# Main.net
KiCad netlist of a schematic drawn in Altium Designer
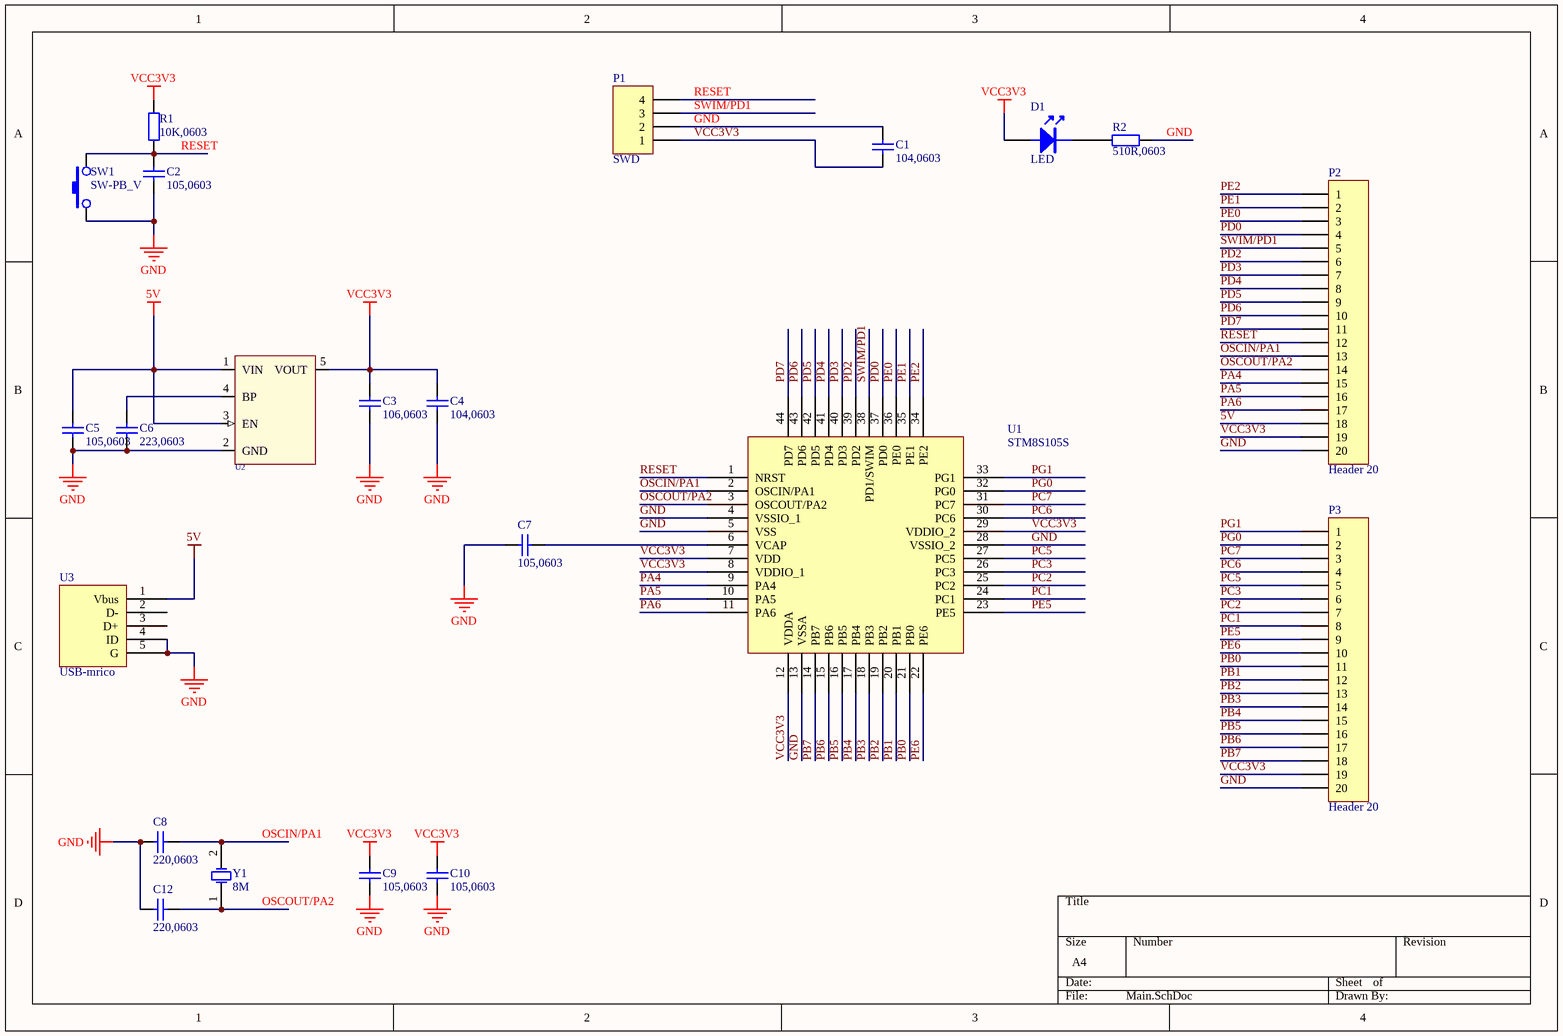
[diagram p0: Main.SchDoc]

(export (version "E")
  (design (tool "Eeschema 10.0.6"))
  (components
    (comp (ref "C1")
      (value "104,0603")
      (footprint "C 0603")
      (description "Capacitor")
      (fields (field (name "PUBLISHER") "Altium Limited"))
      (libsource (lib "STM32F103C8T6") (part "Cap"))
    )
    (comp (ref "C2")
      (value "105,0603")
      (footprint "C 0603")
      (description "Capacitor")
      (fields (field (name "PUBLISHER") "Altium Limited"))
      (libsource (lib "STM32F103C8T6") (part "Cap"))
    )
    (comp (ref "C3")
      (value "106,0603")
      (footprint "C 0603")
      (description "Capacitor")
      (fields (field (name "PUBLISHER") "Altium Limited"))
      (libsource (lib "STM32F103C8T6") (part "Cap"))
    )
    (comp (ref "C4")
      (value "104,0603")
      (footprint "C 0603")
      (description "Capacitor")
      (fields (field (name "PUBLISHER") "Altium Limited"))
      (libsource (lib "STM32F103C8T6") (part "Cap"))
    )
    (comp (ref "C5")
      (value "105,0603")
      (footprint "C 0603")
      (description "Capacitor")
      (fields (field (name "PUBLISHER") "Altium Limited"))
      (libsource (lib "STM32F103C8T6") (part "Cap"))
    )
    (comp (ref "C6")
      (value "223,0603")
      (footprint "C 0603")
      (description "Capacitor")
      (fields (field (name "PUBLISHER") "Altium Limited"))
      (libsource (lib "STM32F103C8T6") (part "Cap"))
    )
    (comp (ref "C7")
      (value "105,0603")
      (footprint "C 0603")
      (description "Capacitor")
      (fields (field (name "PUBLISHER") "Altium Limited"))
      (libsource (lib "STM32F103C8T6") (part "Cap"))
    )
    (comp (ref "C8")
      (value "220,0603")
      (footprint "C 0603")
      (description "Capacitor")
      (fields (field (name "PUBLISHER") "Altium Limited"))
      (libsource (lib "STM32F103C8T6") (part "Cap"))
    )
    (comp (ref "C9")
      (value "105,0603")
      (footprint "C 0603")
      (description "Capacitor")
      (fields (field (name "PUBLISHER") "Altium Limited"))
      (libsource (lib "STM32F103C8T6") (part "Cap"))
    )
    (comp (ref "C10")
      (value "105,0603")
      (footprint "C 0603")
      (description "Capacitor")
      (fields (field (name "PUBLISHER") "Altium Limited"))
      (libsource (lib "STM32F103C8T6") (part "Cap"))
    )
    (comp (ref "C12")
      (value "220,0603")
      (footprint "C 0603")
      (description "Capacitor")
      (fields (field (name "PUBLISHER") "Altium Limited"))
      (libsource (lib "STM32F103C8T6") (part "Cap"))
    )
    (comp (ref "D1") (value "LED") (footprint "LED 0805G") (libsource (lib "STM32F103C8T6") (part "LED")))
    (comp (ref "P1")
      (value "SWD")
      (footprint "HDR-1X4_H")
      (description "Header, 4-Pin")
      (fields (field (name "PUBLISHER") "Altium Limited"))
      (libsource (lib "STM32F103C8T6") (part "Header 4"))
    )
    (comp (ref "P2")
      (value "Header 20")
      (footprint "HDR1X20")
      (description "Header, 20-Pin")
      (fields (field (name "PUBLISHER") "Altium Limited"))
      (libsource (lib "PCB") (part "Header 20"))
    )
    (comp (ref "P3")
      (value "Header 20")
      (footprint "HDR1X20")
      (description "Header, 20-Pin")
      (fields (field (name "PUBLISHER") "Altium Limited"))
      (libsource (lib "PCB") (part "Header 20"))
    )
    (comp (ref "R1")
      (value "10K,0603")
      (footprint "R 0603")
      (description "Resistor")
      (fields (field (name "PUBLISHER") "Altium Limited"))
      (libsource (lib "") (part "Res2_1"))
    )
    (comp (ref "R2")
      (value "510R,0603")
      (footprint "R 0603")
      (description "Resistor")
      (fields (field (name "PUBLISHER") "Altium Limited"))
      (libsource (lib "STM32F103C8T6") (part "Res2"))
    )
    (comp (ref "SW1")
      (value "SW-PB_V")
      (footprint "TSW SMD-3*6*2.5")
      (description "SWITCH")
      (libsource (lib "STM32F103C8T6") (part "SW-PB_V"))
    )
    (comp (ref "U1") (value "STM8S105S") (footprint "PCB:LQFP44") (libsource (lib "PCB") (part "STM8S105S4")))
    (comp (ref "U2")
      (value "RT9193")
      (footprint "SOT23-5L")
      (fields (field (name "ICA_PARTNUM") "$$2191094$$RT9193-15CU5") (field (name "PART NUMBER") "TMP-13"))
      (libsource (lib "STM32F103C8T6") (part "RT9193X_5P"))
    )
    (comp (ref "U3")
      (value "USB-mrico")
      (footprint "USB-micro_B")
      (libsource (lib "PCB_Project_4") (part "usb-STM"))
    )
    (comp (ref "Y1")
      (value "8M")
      (footprint "XTAL-5032")
      (description "Crystal Oscillator")
      (fields (field (name "PUBLISHER") "Altium Limited"))
      (libsource (lib "PCB_Project_4") (part "XTAL"))
    )
  )
  (nets
    (net (code "1") (name "/OSCIN{slash}PA1") (class "Default")
      (node (ref "C8") (pin "1") (pinfunction "1_1") (pintype "passive"))
      (node (ref "P2") (pin "13") (pinfunction "13_13") (pintype "passive"))
      (node (ref "U1") (pin "2") (pinfunction "OSCIN/PA1_2") (pintype "passive"))
      (node (ref "Y1") (pin "2") (pinfunction "OSC2_2") (pintype "passive"))
    )
    (net (code "2") (name "/OSCOUT{slash}PA2") (class "Default")
      (node (ref "C12") (pin "1") (pinfunction "1_1") (pintype "passive"))
      (node (ref "P2") (pin "14") (pinfunction "14_14") (pintype "passive"))
      (node (ref "U1") (pin "3") (pinfunction "OSCOUT/PA2_3") (pintype "passive"))
      (node (ref "Y1") (pin "1") (pinfunction "OSC1_1") (pintype "passive"))
    )
    (net (code "3") (name "/PA4") (class "Default")
      (node (ref "P2") (pin "15") (pinfunction "15_15") (pintype "passive"))
      (node (ref "U1") (pin "9") (pinfunction "PA4_9") (pintype "passive"))
    )
    (net (code "4") (name "/PA5") (class "Default")
      (node (ref "P2") (pin "16") (pinfunction "16_16") (pintype "passive"))
      (node (ref "U1") (pin "10") (pinfunction "PA5_10") (pintype "passive"))
    )
    (net (code "5") (name "/PA6") (class "Default")
      (node (ref "P2") (pin "17") (pinfunction "17_17") (pintype "passive"))
      (node (ref "U1") (pin "11") (pinfunction "PA6_11") (pintype "passive"))
    )
    (net (code "6") (name "/PB0") (class "Default")
      (node (ref "P3") (pin "11") (pinfunction "11_11") (pintype "passive"))
      (node (ref "U1") (pin "21") (pinfunction "PB0_21") (pintype "passive"))
    )
    (net (code "7") (name "/PB1") (class "Default")
      (node (ref "P3") (pin "12") (pinfunction "12_12") (pintype "passive"))
      (node (ref "U1") (pin "20") (pinfunction "PB1_20") (pintype "passive"))
    )
    (net (code "8") (name "/PB2") (class "Default")
      (node (ref "P3") (pin "13") (pinfunction "13_13") (pintype "passive"))
      (node (ref "U1") (pin "19") (pinfunction "PB2_19") (pintype "passive"))
    )
    (net (code "9") (name "/PB3") (class "Default")
      (node (ref "P3") (pin "14") (pinfunction "14_14") (pintype "passive"))
      (node (ref "U1") (pin "18") (pinfunction "PB3_18") (pintype "passive"))
    )
    (net (code "10") (name "/PB4") (class "Default")
      (node (ref "P3") (pin "15") (pinfunction "15_15") (pintype "passive"))
      (node (ref "U1") (pin "17") (pinfunction "PB4_17") (pintype "passive"))
    )
    (net (code "11") (name "/PB5") (class "Default")
      (node (ref "P3") (pin "16") (pinfunction "16_16") (pintype "passive"))
      (node (ref "U1") (pin "16") (pinfunction "PB5_16") (pintype "passive"))
    )
    (net (code "12") (name "/PB6") (class "Default")
      (node (ref "P3") (pin "17") (pinfunction "17_17") (pintype "passive"))
      (node (ref "U1") (pin "15") (pinfunction "PB6_15") (pintype "passive"))
    )
    (net (code "13") (name "/PB7") (class "Default")
      (node (ref "P3") (pin "18") (pinfunction "18_18") (pintype "passive"))
      (node (ref "U1") (pin "14") (pinfunction "PB7_14") (pintype "passive"))
    )
    (net (code "14") (name "/PC1") (class "Default")
      (node (ref "P3") (pin "8") (pinfunction "8_8") (pintype "passive"))
      (node (ref "U1") (pin "24") (pinfunction "PC1_24") (pintype "passive"))
    )
    (net (code "15") (name "/PC2") (class "Default")
      (node (ref "P3") (pin "7") (pinfunction "7_7") (pintype "passive"))
      (node (ref "U1") (pin "25") (pinfunction "PC2_25") (pintype "passive"))
    )
    (net (code "16") (name "/PC3") (class "Default")
      (node (ref "P3") (pin "6") (pinfunction "6_6") (pintype "passive"))
      (node (ref "U1") (pin "26") (pinfunction "PC3_26") (pintype "passive"))
    )
    (net (code "17") (name "/PC5") (class "Default")
      (node (ref "P3") (pin "5") (pinfunction "5_5") (pintype "passive"))
      (node (ref "U1") (pin "27") (pinfunction "PC5_27") (pintype "passive"))
    )
    (net (code "18") (name "/PC6") (class "Default")
      (node (ref "P3") (pin "4") (pinfunction "4_4") (pintype "passive"))
      (node (ref "U1") (pin "30") (pinfunction "PC6_30") (pintype "passive"))
    )
    (net (code "19") (name "/PC7") (class "Default")
      (node (ref "P3") (pin "3") (pinfunction "3_3") (pintype "passive"))
      (node (ref "U1") (pin "31") (pinfunction "PC7_31") (pintype "passive"))
    )
    (net (code "20") (name "/PD0") (class "Default")
      (node (ref "P2") (pin "4") (pinfunction "4_4") (pintype "passive"))
      (node (ref "U1") (pin "37") (pinfunction "PD0_37") (pintype "passive"))
    )
    (net (code "21") (name "/PD2") (class "Default")
      (node (ref "P2") (pin "6") (pinfunction "6_6") (pintype "passive"))
      (node (ref "U1") (pin "39") (pinfunction "PD2_39") (pintype "passive"))
    )
    (net (code "22") (name "/PD3") (class "Default")
      (node (ref "P2") (pin "7") (pinfunction "7_7") (pintype "passive"))
      (node (ref "U1") (pin "40") (pinfunction "PD3_40") (pintype "passive"))
    )
    (net (code "23") (name "/PD4") (class "Default")
      (node (ref "P2") (pin "8") (pinfunction "8_8") (pintype "passive"))
      (node (ref "U1") (pin "41") (pinfunction "PD4_41") (pintype "passive"))
    )
    (net (code "24") (name "/PD5") (class "Default")
      (node (ref "P2") (pin "9") (pinfunction "9_9") (pintype "passive"))
      (node (ref "U1") (pin "42") (pinfunction "PD5_42") (pintype "passive"))
    )
    (net (code "25") (name "/PD6") (class "Default")
      (node (ref "P2") (pin "10") (pinfunction "10_10") (pintype "passive"))
      (node (ref "U1") (pin "43") (pinfunction "PD6_43") (pintype "passive"))
    )
    (net (code "26") (name "/PD7") (class "Default")
      (node (ref "P2") (pin "11") (pinfunction "11_11") (pintype "passive"))
      (node (ref "U1") (pin "44") (pinfunction "PD7_44") (pintype "passive"))
    )
    (net (code "27") (name "/PE0") (class "Default")
      (node (ref "P2") (pin "3") (pinfunction "3_3") (pintype "passive"))
      (node (ref "U1") (pin "36") (pinfunction "PE0_36") (pintype "passive"))
    )
    (net (code "28") (name "/PE1") (class "Default")
      (node (ref "P2") (pin "2") (pinfunction "2_2") (pintype "passive"))
      (node (ref "U1") (pin "35") (pinfunction "PE1_35") (pintype "passive"))
    )
    (net (code "29") (name "/PE2") (class "Default")
      (node (ref "P2") (pin "1") (pinfunction "1_1") (pintype "passive"))
      (node (ref "U1") (pin "34") (pinfunction "PE2_34") (pintype "passive"))
    )
    (net (code "30") (name "/PE5") (class "Default")
      (node (ref "P3") (pin "9") (pinfunction "9_9") (pintype "passive"))
      (node (ref "U1") (pin "23") (pinfunction "PE5_23") (pintype "passive"))
    )
    (net (code "31") (name "/PE6") (class "Default")
      (node (ref "P3") (pin "10") (pinfunction "10_10") (pintype "passive"))
      (node (ref "U1") (pin "22") (pinfunction "PE6_22") (pintype "passive"))
    )
    (net (code "32") (name "/PG0") (class "Default")
      (node (ref "P3") (pin "2") (pinfunction "2_2") (pintype "passive"))
      (node (ref "U1") (pin "32") (pinfunction "PG0_32") (pintype "passive"))
    )
    (net (code "33") (name "/PG1") (class "Default")
      (node (ref "P3") (pin "1") (pinfunction "1_1") (pintype "passive"))
      (node (ref "U1") (pin "33") (pinfunction "PG1_33") (pintype "passive"))
    )
    (net (code "34") (name "/RESET") (class "Default")
      (node (ref "C2") (pin "2") (pinfunction "2_2") (pintype "passive"))
      (node (ref "P1") (pin "4") (pinfunction "4_4") (pintype "passive"))
      (node (ref "P2") (pin "12") (pinfunction "12_12") (pintype "passive"))
      (node (ref "R1") (pin "1") (pinfunction "1_1") (pintype "passive"))
      (node (ref "SW1") (pin "2") (pinfunction "2_2") (pintype "passive"))
      (node (ref "U1") (pin "1") (pinfunction "NRST_1") (pintype "passive"))
    )
    (net (code "35") (name "/SWIM{slash}PD1") (class "Default")
      (node (ref "P1") (pin "3") (pinfunction "3_3") (pintype "passive"))
      (node (ref "P2") (pin "5") (pinfunction "5_5") (pintype "passive"))
      (node (ref "U1") (pin "38") (pinfunction "PD1/SWIM_38") (pintype "passive"))
    )
    (net (code "36") (name "5V") (class "Default")
      (node (ref "C5") (pin "2") (pinfunction "2_2") (pintype "passive"))
      (node (ref "P2") (pin "18") (pinfunction "18_18") (pintype "passive"))
      (node (ref "U2") (pin "1") (pinfunction "VIN_1") (pintype "power_in"))
      (node (ref "U2") (pin "3") (pinfunction "EN_3") (pintype "input"))
      (node (ref "U3") (pin "1") (pinfunction "Vbus_1") (pintype "passive"))
    )
    (net (code "37") (name "GND") (class "Default")
      (node (ref "C1") (pin "2") (pinfunction "2_2") (pintype "passive"))
      (node (ref "C10") (pin "1") (pinfunction "1_1") (pintype "passive"))
      (node (ref "C12") (pin "2") (pinfunction "2_2") (pintype "passive"))
      (node (ref "C2") (pin "1") (pinfunction "1_1") (pintype "passive"))
      (node (ref "C3") (pin "2") (pinfunction "2_2") (pintype "passive"))
      (node (ref "C4") (pin "1") (pinfunction "1_1") (pintype "passive"))
      (node (ref "C5") (pin "1") (pinfunction "1_1") (pintype "passive"))
      (node (ref "C6") (pin "1") (pinfunction "1_1") (pintype "passive"))
      (node (ref "C7") (pin "2") (pinfunction "2_2") (pintype "passive"))
      (node (ref "C8") (pin "2") (pinfunction "2_2") (pintype "passive"))
      (node (ref "C9") (pin "1") (pinfunction "1_1") (pintype "passive"))
      (node (ref "P1") (pin "2") (pinfunction "2_2") (pintype "passive"))
      (node (ref "P2") (pin "20") (pinfunction "20_20") (pintype "passive"))
      (node (ref "P3") (pin "20") (pinfunction "20_20") (pintype "passive"))
      (node (ref "R2") (pin "2") (pinfunction "2_2") (pintype "passive"))
      (node (ref "SW1") (pin "1") (pinfunction "1_1") (pintype "passive"))
      (node (ref "U1") (pin "13") (pinfunction "VSSA_13") (pintype "passive"))
      (node (ref "U1") (pin "28") (pinfunction "VSSIO_2_28") (pintype "passive"))
      (node (ref "U1") (pin "4") (pinfunction "VSSIO_1_4") (pintype "passive"))
      (node (ref "U1") (pin "5") (pinfunction "VSS_5") (pintype "passive"))
      (node (ref "U2") (pin "2") (pinfunction "GND_2") (pintype "power_in"))
      (node (ref "U3") (pin "4") (pinfunction "ID_4") (pintype "passive"))
      (node (ref "U3") (pin "5") (pinfunction "G_5") (pintype "passive"))
    )
    (net (code "38") (name "Net-(D1-Pad2)") (class "Default")
      (node (ref "D1") (pin "2") (pinfunction "2_2") (pintype "passive"))
      (node (ref "R2") (pin "1") (pinfunction "1_1") (pintype "passive"))
    )
    (net (code "39") (name "Net-(U1-VCAP)") (class "Default")
      (node (ref "C7") (pin "1") (pinfunction "1_1") (pintype "passive"))
      (node (ref "U1") (pin "6") (pinfunction "VCAP_6") (pintype "passive"))
    )
    (net (code "40") (name "Net-(U2-BP)") (class "Default")
      (node (ref "C6") (pin "2") (pinfunction "2_2") (pintype "passive"))
      (node (ref "U2") (pin "4") (pinfunction "BP_4") (pintype "passive"))
    )
    (net (code "41") (name "VCC3V3") (class "Default")
      (node (ref "C1") (pin "1") (pinfunction "1_1") (pintype "passive"))
      (node (ref "C10") (pin "2") (pinfunction "2_2") (pintype "passive"))
      (node (ref "C3") (pin "1") (pinfunction "1_1") (pintype "passive"))
      (node (ref "C4") (pin "2") (pinfunction "2_2") (pintype "passive"))
      (node (ref "C9") (pin "2") (pinfunction "2_2") (pintype "passive"))
      (node (ref "D1") (pin "1") (pinfunction "1_1") (pintype "passive"))
      (node (ref "P1") (pin "1") (pinfunction "1_1") (pintype "passive"))
      (node (ref "P2") (pin "19") (pinfunction "19_19") (pintype "passive"))
      (node (ref "P3") (pin "19") (pinfunction "19_19") (pintype "passive"))
      (node (ref "R1") (pin "2") (pinfunction "2_2") (pintype "passive"))
      (node (ref "U1") (pin "12") (pinfunction "VDDA_12") (pintype "passive"))
      (node (ref "U1") (pin "29") (pinfunction "VDDIO_2_29") (pintype "passive"))
      (node (ref "U1") (pin "7") (pinfunction "VDD_7") (pintype "passive"))
      (node (ref "U1") (pin "8") (pinfunction "VDDIO_1_8") (pintype "passive"))
      (node (ref "U2") (pin "5") (pinfunction "VOUT_5") (pintype "power_in"))
    )
    (net (code "42") (name "unconnected-(U3-D+-Pad3)") (class "Default")
      (node (ref "U3") (pin "3") (pinfunction "D+_3") (pintype "passive"))
    )
    (net (code "43") (name "unconnected-(U3-D--Pad2)") (class "Default")
      (node (ref "U3") (pin "2") (pinfunction "D-_2") (pintype "passive"))
    )
  )
)
